# LED_Matrix.net
KiCad netlist of a schematic drawn in EAGLE
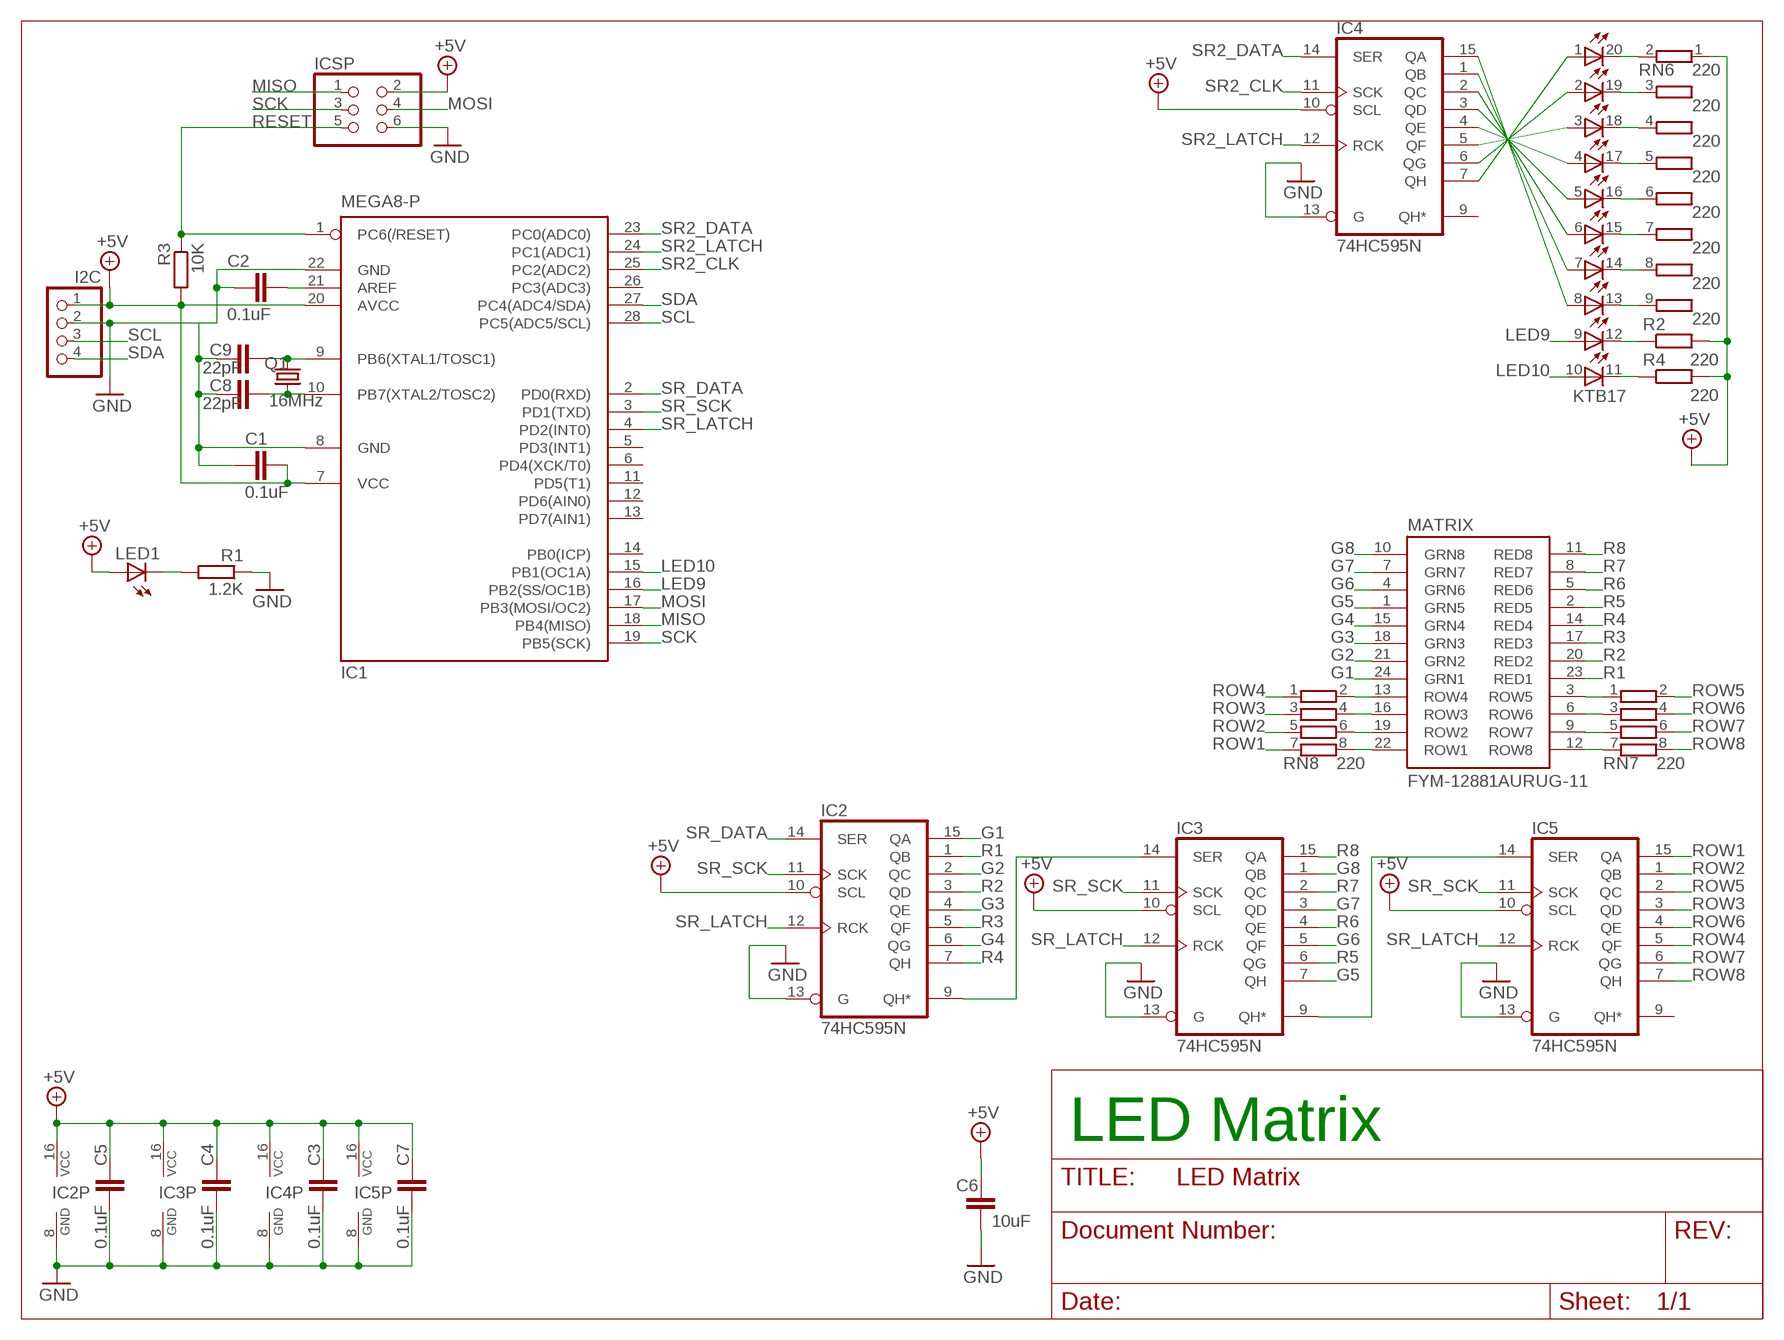
[diagram p0: schematic, sheet 1]

(export (version "E")
  (design (tool "Eeschema 10.0.6"))
  (components
    (comp (ref "-")
      (value "KTB17")
      (footprint "eagle-import:LB10")
      (libsource (lib "eagle-import") (part "LB10"))
    )
    (comp (ref "C1")
      (value "0.1uF")
      (footprint "eagle-import:C025-024X044")
      (libsource (lib "eagle-import") (part "C-EU025-024X044"))
    )
    (comp (ref "C2")
      (value "0.1uF")
      (footprint "eagle-import:C025-024X044")
      (libsource (lib "eagle-import") (part "C-EU025-024X044"))
    )
    (comp (ref "C3")
      (value "0.1uF")
      (footprint "eagle-import:C025-024X044")
      (libsource (lib "eagle-import") (part "C-EU025-024X044"))
    )
    (comp (ref "C4")
      (value "0.1uF")
      (footprint "eagle-import:C025-024X044")
      (libsource (lib "eagle-import") (part "C-EU025-024X044"))
    )
    (comp (ref "C5")
      (value "0.1uF")
      (footprint "eagle-import:C025-024X044")
      (libsource (lib "eagle-import") (part "C-EU025-024X044"))
    )
    (comp (ref "C6")
      (value "10uF")
      (footprint "eagle-import:C025-024X044")
      (libsource (lib "eagle-import") (part "C-EU025-024X044"))
    )
    (comp (ref "C7")
      (value "0.1uF")
      (footprint "eagle-import:C025-024X044")
      (libsource (lib "eagle-import") (part "C-EU025-024X044"))
    )
    (comp (ref "C8")
      (value "22pF")
      (footprint "eagle-import:C025-024X044")
      (libsource (lib "eagle-import") (part "C-EU025-024X044"))
    )
    (comp (ref "C9")
      (value "22pF")
      (footprint "eagle-import:C025-024X044")
      (libsource (lib "eagle-import") (part "C-EU025-024X044"))
    )
    (comp (ref "I2C")
      (value "PINHD-1X4")
      (footprint "eagle-import:1X04")
      (libsource (lib "eagle-import") (part "PINHD-1X4"))
    )
    (comp (ref "IC1")
      (value "MEGA8-P")
      (footprint "eagle-import:DIL28-3")
      (libsource (lib "eagle-import") (part "MEGA8-P"))
    )
    (comp (ref "IC2")
      (value "74HC595N")
      (footprint "eagle-import:DIL16")
      (libsource (lib "eagle-import") (part "74595NHC"))
    )
    (comp (ref "IC3")
      (value "74HC595N")
      (footprint "eagle-import:DIL16")
      (libsource (lib "eagle-import") (part "74595NHC"))
    )
    (comp (ref "IC4")
      (value "74HC595N")
      (footprint "eagle-import:DIL16")
      (libsource (lib "eagle-import") (part "74595NHC"))
    )
    (comp (ref "IC5")
      (value "74HC595N")
      (footprint "eagle-import:DIL16")
      (libsource (lib "eagle-import") (part "74595NHC"))
    )
    (comp (ref "ICSP")
      (value "PINHD-2X3")
      (footprint "eagle-import:2X03")
      (libsource (lib "eagle-import") (part "PINHD-2X3"))
    )
    (comp (ref "LED1")
      (value "LED5MM")
      (footprint "eagle-import:LED5MM")
      (libsource (lib "eagle-import") (part "LED5MM"))
    )
    (comp (ref "MATRIX")
      (value "FYM-12881AURUG-11")
      (footprint "eagle-import:YSM-1288CR3G2C")
      (libsource (lib "eagle-import") (part "YSM-1288CR3G2C"))
    )
    (comp (ref "Q1")
      (value "16MHz")
      (footprint "eagle-import:HC49_S")
      (libsource (lib "eagle-import") (part "CRYSTALHC49S"))
    )
    (comp (ref "R1")
      (value "1.2K")
      (footprint "eagle-import:0207_2V")
      (libsource (lib "eagle-import") (part "R-EU_0207/2V"))
    )
    (comp (ref "R2")
      (value "220")
      (footprint "eagle-import:0207_2V")
      (libsource (lib "eagle-import") (part "R-EU_0207/2V"))
    )
    (comp (ref "R3")
      (value "10K")
      (footprint "eagle-import:0207_2V")
      (libsource (lib "eagle-import") (part "R-EU_0207/2V"))
    )
    (comp (ref "R4")
      (value "220")
      (footprint "eagle-import:0207_2V")
      (libsource (lib "eagle-import") (part "R-EU_0207/2V"))
    )
    (comp (ref "RN6")
      (value "220")
      (footprint "eagle-import:SIL9")
      (libsource (lib "eagle-import") (part "GE08RP"))
    )
    (comp (ref "RN7")
      (value "220")
      (footprint "eagle-import:SIL8")
      (libsource (lib "eagle-import") (part "E4RP"))
    )
    (comp (ref "RN8")
      (value "220")
      (footprint "eagle-import:SIL8")
      (libsource (lib "eagle-import") (part "E4RP"))
    )
  )
  (nets
    (net (code "1") (name "+5V") (class "Default")
      (node (ref "C1") (pin "2") (pinfunction "2_2") (pintype "passive"))
      (node (ref "C3") (pin "1") (pinfunction "1_1") (pintype "passive"))
      (node (ref "C4") (pin "1") (pinfunction "1_1") (pintype "passive"))
      (node (ref "C5") (pin "1") (pinfunction "1_1") (pintype "passive"))
      (node (ref "C6") (pin "1") (pinfunction "1_1") (pintype "passive"))
      (node (ref "C7") (pin "1") (pinfunction "1_1") (pintype "passive"))
      (node (ref "I2C") (pin "1") (pinfunction "1_1") (pintype "passive"))
      (node (ref "IC1") (pin "20") (pinfunction "AVCC_20") (pintype "power_in"))
      (node (ref "IC1") (pin "7") (pinfunction "VCC_7") (pintype "power_in"))
      (node (ref "IC2") (pin "10") (pinfunction "SCL_10") (pintype "input"))
      (node (ref "IC2") (pin "16") (pinfunction "VCC_16") (pintype "power_in"))
      (node (ref "IC3") (pin "10") (pinfunction "SCL_10") (pintype "input"))
      (node (ref "IC3") (pin "16") (pinfunction "VCC_16") (pintype "power_in"))
      (node (ref "IC4") (pin "10") (pinfunction "SCL_10") (pintype "input"))
      (node (ref "IC4") (pin "16") (pinfunction "VCC_16") (pintype "power_in"))
      (node (ref "IC5") (pin "10") (pinfunction "SCL_10") (pintype "input"))
      (node (ref "IC5") (pin "16") (pinfunction "VCC_16") (pintype "power_in"))
      (node (ref "ICSP") (pin "2") (pinfunction "2_2") (pintype "passive"))
      (node (ref "LED1") (pin "A") (pinfunction "A_A") (pintype "passive"))
      (node (ref "R2") (pin "2") (pinfunction "2_2") (pintype "passive"))
      (node (ref "R3") (pin "2") (pinfunction "2_2") (pintype "passive"))
      (node (ref "R4") (pin "2") (pinfunction "2_2") (pintype "passive"))
      (node (ref "RN6") (pin "1") (pinfunction "1_1") (pintype "passive"))
    )
    (net (code "2") (name "/G1") (class "Default")
      (node (ref "IC2") (pin "15") (pinfunction "QA_15") (pintype "tri_state"))
      (node (ref "MATRIX") (pin "24") (pinfunction "GRN1_24") (pintype "bidirectional"))
    )
    (net (code "3") (name "/G2") (class "Default")
      (node (ref "IC2") (pin "2") (pinfunction "QC_2") (pintype "tri_state"))
      (node (ref "MATRIX") (pin "21") (pinfunction "GRN2_21") (pintype "bidirectional"))
    )
    (net (code "4") (name "/G3") (class "Default")
      (node (ref "IC2") (pin "4") (pinfunction "QE_4") (pintype "tri_state"))
      (node (ref "MATRIX") (pin "18") (pinfunction "GRN3_18") (pintype "bidirectional"))
    )
    (net (code "5") (name "/G4") (class "Default")
      (node (ref "IC2") (pin "6") (pinfunction "QG_6") (pintype "tri_state"))
      (node (ref "MATRIX") (pin "15") (pinfunction "GRN4_15") (pintype "bidirectional"))
    )
    (net (code "6") (name "/G5") (class "Default")
      (node (ref "IC3") (pin "7") (pinfunction "QH_7") (pintype "tri_state"))
      (node (ref "MATRIX") (pin "1") (pinfunction "GRN5_1") (pintype "bidirectional"))
    )
    (net (code "7") (name "/G6") (class "Default")
      (node (ref "IC3") (pin "5") (pinfunction "QF_5") (pintype "tri_state"))
      (node (ref "MATRIX") (pin "4") (pinfunction "GRN6_4") (pintype "bidirectional"))
    )
    (net (code "8") (name "/G7") (class "Default")
      (node (ref "IC3") (pin "3") (pinfunction "QD_3") (pintype "tri_state"))
      (node (ref "MATRIX") (pin "7") (pinfunction "GRN7_7") (pintype "bidirectional"))
    )
    (net (code "9") (name "/G8") (class "Default")
      (node (ref "IC3") (pin "1") (pinfunction "QB_1") (pintype "tri_state"))
      (node (ref "MATRIX") (pin "10") (pinfunction "GRN8_10") (pintype "bidirectional"))
    )
    (net (code "10") (name "/LED9") (class "Default")
      (node (ref "-") (pin "9") (pinfunction "A_9") (pintype "passive"))
      (node (ref "IC1") (pin "16") (pinfunction "PB2(SS/OC1B)_16") (pintype "bidirectional"))
    )
    (net (code "11") (name "/LED10") (class "Default")
      (node (ref "-") (pin "10") (pinfunction "A_10") (pintype "passive"))
      (node (ref "IC1") (pin "15") (pinfunction "PB1(OC1A)_15") (pintype "bidirectional"))
    )
    (net (code "12") (name "/MISO") (class "Default")
      (node (ref "IC1") (pin "18") (pinfunction "PB4(MISO)_18") (pintype "bidirectional"))
      (node (ref "ICSP") (pin "1") (pinfunction "1_1") (pintype "passive"))
    )
    (net (code "13") (name "/MOSI") (class "Default")
      (node (ref "IC1") (pin "17") (pinfunction "PB3(MOSI/OC2)_17") (pintype "bidirectional"))
      (node (ref "ICSP") (pin "4") (pinfunction "4_4") (pintype "passive"))
    )
    (net (code "14") (name "/R1") (class "Default")
      (node (ref "IC2") (pin "1") (pinfunction "QB_1") (pintype "tri_state"))
      (node (ref "MATRIX") (pin "23") (pinfunction "RED1_23") (pintype "bidirectional"))
    )
    (net (code "15") (name "/R2") (class "Default")
      (node (ref "IC2") (pin "3") (pinfunction "QD_3") (pintype "tri_state"))
      (node (ref "MATRIX") (pin "20") (pinfunction "RED2_20") (pintype "bidirectional"))
    )
    (net (code "16") (name "/R3") (class "Default")
      (node (ref "IC2") (pin "5") (pinfunction "QF_5") (pintype "tri_state"))
      (node (ref "MATRIX") (pin "17") (pinfunction "RED3_17") (pintype "bidirectional"))
    )
    (net (code "17") (name "/R4") (class "Default")
      (node (ref "IC2") (pin "7") (pinfunction "QH_7") (pintype "tri_state"))
      (node (ref "MATRIX") (pin "14") (pinfunction "RED4_14") (pintype "bidirectional"))
    )
    (net (code "18") (name "/R5") (class "Default")
      (node (ref "IC3") (pin "6") (pinfunction "QG_6") (pintype "tri_state"))
      (node (ref "MATRIX") (pin "2") (pinfunction "RED5_2") (pintype "bidirectional"))
    )
    (net (code "19") (name "/R6") (class "Default")
      (node (ref "IC3") (pin "4") (pinfunction "QE_4") (pintype "tri_state"))
      (node (ref "MATRIX") (pin "5") (pinfunction "RED6_5") (pintype "bidirectional"))
    )
    (net (code "20") (name "/R7") (class "Default")
      (node (ref "IC3") (pin "2") (pinfunction "QC_2") (pintype "tri_state"))
      (node (ref "MATRIX") (pin "8") (pinfunction "RED7_8") (pintype "bidirectional"))
    )
    (net (code "21") (name "/R8") (class "Default")
      (node (ref "IC3") (pin "15") (pinfunction "QA_15") (pintype "tri_state"))
      (node (ref "MATRIX") (pin "11") (pinfunction "RED8_11") (pintype "bidirectional"))
    )
    (net (code "22") (name "/RESET") (class "Default")
      (node (ref "IC1") (pin "1") (pinfunction "PC6(/RESET)_1") (pintype "bidirectional"))
      (node (ref "ICSP") (pin "5") (pinfunction "5_5") (pintype "passive"))
      (node (ref "R3") (pin "1") (pinfunction "1_1") (pintype "passive"))
    )
    (net (code "23") (name "/ROW1") (class "Default")
      (node (ref "IC5") (pin "15") (pinfunction "QA_15") (pintype "tri_state"))
      (node (ref "RN8") (pin "7") (pinfunction "1_7") (pintype "passive"))
    )
    (net (code "24") (name "/ROW2") (class "Default")
      (node (ref "IC5") (pin "1") (pinfunction "QB_1") (pintype "tri_state"))
      (node (ref "RN8") (pin "5") (pinfunction "1_5") (pintype "passive"))
    )
    (net (code "25") (name "/ROW3") (class "Default")
      (node (ref "IC5") (pin "3") (pinfunction "QD_3") (pintype "tri_state"))
      (node (ref "RN8") (pin "3") (pinfunction "1_3") (pintype "passive"))
    )
    (net (code "26") (name "/ROW4") (class "Default")
      (node (ref "IC5") (pin "5") (pinfunction "QF_5") (pintype "tri_state"))
      (node (ref "RN8") (pin "1") (pinfunction "1_1") (pintype "passive"))
    )
    (net (code "27") (name "/ROW5") (class "Default")
      (node (ref "IC5") (pin "2") (pinfunction "QC_2") (pintype "tri_state"))
      (node (ref "RN7") (pin "2") (pinfunction "2_2") (pintype "passive"))
    )
    (net (code "28") (name "/ROW6") (class "Default")
      (node (ref "IC5") (pin "4") (pinfunction "QE_4") (pintype "tri_state"))
      (node (ref "RN7") (pin "4") (pinfunction "2_4") (pintype "passive"))
    )
    (net (code "29") (name "/ROW7") (class "Default")
      (node (ref "IC5") (pin "6") (pinfunction "QG_6") (pintype "tri_state"))
      (node (ref "RN7") (pin "6") (pinfunction "2_6") (pintype "passive"))
    )
    (net (code "30") (name "/ROW8") (class "Default")
      (node (ref "IC5") (pin "7") (pinfunction "QH_7") (pintype "tri_state"))
      (node (ref "RN7") (pin "8") (pinfunction "2_8") (pintype "passive"))
    )
    (net (code "31") (name "/SCK") (class "Default")
      (node (ref "IC1") (pin "19") (pinfunction "PB5(SCK)_19") (pintype "bidirectional"))
      (node (ref "ICSP") (pin "3") (pinfunction "3_3") (pintype "passive"))
    )
    (net (code "32") (name "/SCL") (class "Default")
      (node (ref "I2C") (pin "3") (pinfunction "3_3") (pintype "passive"))
      (node (ref "IC1") (pin "28") (pinfunction "PC5(ADC5/SCL)_28") (pintype "bidirectional"))
    )
    (net (code "33") (name "/SDA") (class "Default")
      (node (ref "I2C") (pin "4") (pinfunction "4_4") (pintype "passive"))
      (node (ref "IC1") (pin "27") (pinfunction "PC4(ADC4/SDA)_27") (pintype "bidirectional"))
    )
    (net (code "34") (name "/SR2_CLK") (class "Default")
      (node (ref "IC1") (pin "25") (pinfunction "PC2(ADC2)_25") (pintype "bidirectional"))
      (node (ref "IC4") (pin "11") (pinfunction "SCK_11") (pintype "input"))
    )
    (net (code "35") (name "/SR2_DATA") (class "Default")
      (node (ref "IC1") (pin "23") (pinfunction "PC0(ADC0)_23") (pintype "bidirectional"))
      (node (ref "IC4") (pin "14") (pinfunction "SER_14") (pintype "input"))
    )
    (net (code "36") (name "/SR2_LATCH") (class "Default")
      (node (ref "IC1") (pin "24") (pinfunction "PC1(ADC1)_24") (pintype "bidirectional"))
      (node (ref "IC4") (pin "12") (pinfunction "RCK_12") (pintype "input"))
    )
    (net (code "37") (name "/SR_DATA") (class "Default")
      (node (ref "IC1") (pin "2") (pinfunction "PD0(RXD)_2") (pintype "bidirectional"))
      (node (ref "IC2") (pin "14") (pinfunction "SER_14") (pintype "input"))
    )
    (net (code "38") (name "/SR_LATCH") (class "Default")
      (node (ref "IC1") (pin "4") (pinfunction "PD2(INT0)_4") (pintype "bidirectional"))
      (node (ref "IC2") (pin "12") (pinfunction "RCK_12") (pintype "input"))
      (node (ref "IC3") (pin "12") (pinfunction "RCK_12") (pintype "input"))
      (node (ref "IC5") (pin "12") (pinfunction "RCK_12") (pintype "input"))
    )
    (net (code "39") (name "/SR_SCK") (class "Default")
      (node (ref "IC1") (pin "3") (pinfunction "PD1(TXD)_3") (pintype "bidirectional"))
      (node (ref "IC2") (pin "11") (pinfunction "SCK_11") (pintype "input"))
      (node (ref "IC3") (pin "11") (pinfunction "SCK_11") (pintype "input"))
      (node (ref "IC5") (pin "11") (pinfunction "SCK_11") (pintype "input"))
    )
    (net (code "40") (name "GND") (class "Default")
      (node (ref "C1") (pin "1") (pinfunction "1_1") (pintype "passive"))
      (node (ref "C2") (pin "1") (pinfunction "1_1") (pintype "passive"))
      (node (ref "C3") (pin "2") (pinfunction "2_2") (pintype "passive"))
      (node (ref "C4") (pin "2") (pinfunction "2_2") (pintype "passive"))
      (node (ref "C5") (pin "2") (pinfunction "2_2") (pintype "passive"))
      (node (ref "C6") (pin "2") (pinfunction "2_2") (pintype "passive"))
      (node (ref "C7") (pin "2") (pinfunction "2_2") (pintype "passive"))
      (node (ref "C8") (pin "1") (pinfunction "1_1") (pintype "passive"))
      (node (ref "C9") (pin "1") (pinfunction "1_1") (pintype "passive"))
      (node (ref "I2C") (pin "2") (pinfunction "2_2") (pintype "passive"))
      (node (ref "IC1") (pin "22") (pinfunction "GND_22") (pintype "power_in"))
      (node (ref "IC1") (pin "8") (pinfunction "GND_8") (pintype "power_in"))
      (node (ref "IC2") (pin "13") (pinfunction "G_13") (pintype "input"))
      (node (ref "IC2") (pin "8") (pinfunction "GND_8") (pintype "power_in"))
      (node (ref "IC3") (pin "13") (pinfunction "G_13") (pintype "input"))
      (node (ref "IC3") (pin "8") (pinfunction "GND_8") (pintype "power_in"))
      (node (ref "IC4") (pin "13") (pinfunction "G_13") (pintype "input"))
      (node (ref "IC4") (pin "8") (pinfunction "GND_8") (pintype "power_in"))
      (node (ref "IC5") (pin "13") (pinfunction "G_13") (pintype "input"))
      (node (ref "IC5") (pin "8") (pinfunction "GND_8") (pintype "power_in"))
      (node (ref "ICSP") (pin "6") (pinfunction "6_6") (pintype "passive"))
      (node (ref "R1") (pin "1") (pinfunction "1_1") (pintype "passive"))
    )
    (net (code "41") (name "Net-(-A-A)") (class "Default")
      (node (ref "-") (pin "1") (pinfunction "A_1") (pintype "passive"))
      (node (ref "IC4") (pin "7") (pinfunction "QH_7") (pintype "tri_state"))
    )
    (net (code "42") (name "Net-(-A-C)") (class "Default")
      (node (ref "-") (pin "20") (pinfunction "C_20") (pintype "passive"))
      (node (ref "RN6") (pin "2") (pinfunction "2_2") (pintype "passive"))
    )
    (net (code "43") (name "Net-(-B-C)") (class "Default")
      (node (ref "-") (pin "11") (pinfunction "C_11") (pintype "passive"))
      (node (ref "R4") (pin "1") (pinfunction "1_1") (pintype "passive"))
    )
    (net (code "44") (name "Net-(-C-A)") (class "Default")
      (node (ref "-") (pin "2") (pinfunction "A_2") (pintype "passive"))
      (node (ref "IC4") (pin "6") (pinfunction "QG_6") (pintype "tri_state"))
    )
    (net (code "45") (name "Net-(-C-C)") (class "Default")
      (node (ref "-") (pin "19") (pinfunction "C_19") (pintype "passive"))
      (node (ref "RN6") (pin "3") (pinfunction "2_3") (pintype "passive"))
    )
    (net (code "46") (name "Net-(-D-A)") (class "Default")
      (node (ref "-") (pin "3") (pinfunction "A_3") (pintype "passive"))
      (node (ref "IC4") (pin "5") (pinfunction "QF_5") (pintype "tri_state"))
    )
    (net (code "47") (name "Net-(-D-C)") (class "Default")
      (node (ref "-") (pin "18") (pinfunction "C_18") (pintype "passive"))
      (node (ref "RN6") (pin "4") (pinfunction "2_4") (pintype "passive"))
    )
    (net (code "48") (name "Net-(-E-A)") (class "Default")
      (node (ref "-") (pin "4") (pinfunction "A_4") (pintype "passive"))
      (node (ref "IC4") (pin "4") (pinfunction "QE_4") (pintype "tri_state"))
    )
    (net (code "49") (name "Net-(-E-C)") (class "Default")
      (node (ref "-") (pin "17") (pinfunction "C_17") (pintype "passive"))
      (node (ref "RN6") (pin "5") (pinfunction "2_5") (pintype "passive"))
    )
    (net (code "50") (name "Net-(-F-A)") (class "Default")
      (node (ref "-") (pin "5") (pinfunction "A_5") (pintype "passive"))
      (node (ref "IC4") (pin "3") (pinfunction "QD_3") (pintype "tri_state"))
    )
    (net (code "51") (name "Net-(-F-C)") (class "Default")
      (node (ref "-") (pin "16") (pinfunction "C_16") (pintype "passive"))
      (node (ref "RN6") (pin "6") (pinfunction "2_6") (pintype "passive"))
    )
    (net (code "52") (name "Net-(-G-A)") (class "Default")
      (node (ref "-") (pin "6") (pinfunction "A_6") (pintype "passive"))
      (node (ref "IC4") (pin "2") (pinfunction "QC_2") (pintype "tri_state"))
    )
    (net (code "53") (name "Net-(-G-C)") (class "Default")
      (node (ref "-") (pin "15") (pinfunction "C_15") (pintype "passive"))
      (node (ref "RN6") (pin "7") (pinfunction "2_7") (pintype "passive"))
    )
    (net (code "54") (name "Net-(-H-A)") (class "Default")
      (node (ref "-") (pin "7") (pinfunction "A_7") (pintype "passive"))
      (node (ref "IC4") (pin "1") (pinfunction "QB_1") (pintype "tri_state"))
    )
    (net (code "55") (name "Net-(-H-C)") (class "Default")
      (node (ref "-") (pin "14") (pinfunction "C_14") (pintype "passive"))
      (node (ref "RN6") (pin "8") (pinfunction "2_8") (pintype "passive"))
    )
    (net (code "56") (name "Net-(-I-A)") (class "Default")
      (node (ref "-") (pin "8") (pinfunction "A_8") (pintype "passive"))
      (node (ref "IC4") (pin "15") (pinfunction "QA_15") (pintype "tri_state"))
    )
    (net (code "57") (name "Net-(-I-C)") (class "Default")
      (node (ref "-") (pin "13") (pinfunction "C_13") (pintype "passive"))
      (node (ref "RN6") (pin "9") (pinfunction "2_9") (pintype "passive"))
    )
    (net (code "58") (name "Net-(-J-C)") (class "Default")
      (node (ref "-") (pin "12") (pinfunction "C_12") (pintype "passive"))
      (node (ref "R2") (pin "1") (pinfunction "1_1") (pintype "passive"))
    )
    (net (code "59") (name "Net-(IC1-AREF)") (class "Default")
      (node (ref "C2") (pin "2") (pinfunction "2_2") (pintype "passive"))
      (node (ref "IC1") (pin "21") (pinfunction "AREF_21") (pintype "passive"))
    )
    (net (code "60") (name "Net-(IC1-PB6(XTAL1{slash}TOSC1))") (class "Default")
      (node (ref "C9") (pin "2") (pinfunction "2_2") (pintype "passive"))
      (node (ref "IC1") (pin "9") (pinfunction "PB6(XTAL1/TOSC1)_9") (pintype "bidirectional"))
      (node (ref "Q1") (pin "2") (pinfunction "2_2") (pintype "passive"))
    )
    (net (code "61") (name "Net-(IC1-PB7(XTAL2{slash}TOSC2))") (class "Default")
      (node (ref "C8") (pin "2") (pinfunction "2_2") (pintype "passive"))
      (node (ref "IC1") (pin "10") (pinfunction "PB7(XTAL2/TOSC2)_10") (pintype "bidirectional"))
      (node (ref "Q1") (pin "1") (pinfunction "1_1") (pintype "passive"))
    )
    (net (code "62") (name "Net-(IC2A-QH*)") (class "Default")
      (node (ref "IC2") (pin "9") (pinfunction "QH*_9") (pintype "tri_state"))
      (node (ref "IC3") (pin "14") (pinfunction "SER_14") (pintype "input"))
    )
    (net (code "63") (name "Net-(IC3A-QH*)") (class "Default")
      (node (ref "IC3") (pin "9") (pinfunction "QH*_9") (pintype "tri_state"))
      (node (ref "IC5") (pin "14") (pinfunction "SER_14") (pintype "input"))
    )
    (net (code "64") (name "Net-(LED1-C)") (class "Default")
      (node (ref "LED1") (pin "K") (pinfunction "C_K") (pintype "passive"))
      (node (ref "R1") (pin "2") (pinfunction "2_2") (pintype "passive"))
    )
    (net (code "65") (name "Net-(MATRIX-ROW1)") (class "Default")
      (node (ref "MATRIX") (pin "22") (pinfunction "ROW1_22") (pintype "bidirectional"))
      (node (ref "RN8") (pin "8") (pinfunction "2_8") (pintype "passive"))
    )
    (net (code "66") (name "Net-(MATRIX-ROW2)") (class "Default")
      (node (ref "MATRIX") (pin "19") (pinfunction "ROW2_19") (pintype "bidirectional"))
      (node (ref "RN8") (pin "6") (pinfunction "2_6") (pintype "passive"))
    )
    (net (code "67") (name "Net-(MATRIX-ROW3)") (class "Default")
      (node (ref "MATRIX") (pin "16") (pinfunction "ROW3_16") (pintype "bidirectional"))
      (node (ref "RN8") (pin "4") (pinfunction "2_4") (pintype "passive"))
    )
    (net (code "68") (name "Net-(MATRIX-ROW4)") (class "Default")
      (node (ref "MATRIX") (pin "13") (pinfunction "ROW4_13") (pintype "bidirectional"))
      (node (ref "RN8") (pin "2") (pinfunction "2_2") (pintype "passive"))
    )
    (net (code "69") (name "Net-(MATRIX-ROW5)") (class "Default")
      (node (ref "MATRIX") (pin "3") (pinfunction "ROW5_3") (pintype "bidirectional"))
      (node (ref "RN7") (pin "1") (pinfunction "1_1") (pintype "passive"))
    )
    (net (code "70") (name "Net-(MATRIX-ROW6)") (class "Default")
      (node (ref "MATRIX") (pin "6") (pinfunction "ROW6_6") (pintype "bidirectional"))
      (node (ref "RN7") (pin "3") (pinfunction "1_3") (pintype "passive"))
    )
    (net (code "71") (name "Net-(MATRIX-ROW7)") (class "Default")
      (node (ref "MATRIX") (pin "9") (pinfunction "ROW7_9") (pintype "bidirectional"))
      (node (ref "RN7") (pin "5") (pinfunction "1_5") (pintype "passive"))
    )
    (net (code "72") (name "Net-(MATRIX-ROW8)") (class "Default")
      (node (ref "MATRIX") (pin "12") (pinfunction "ROW8_12") (pintype "bidirectional"))
      (node (ref "RN7") (pin "7") (pinfunction "1_7") (pintype "passive"))
    )
    (net (code "73") (name "unconnected-(IC1-PB0(ICP)-Pad14)") (class "Default")
      (node (ref "IC1") (pin "14") (pinfunction "PB0(ICP)_14") (pintype "bidirectional"))
    )
    (net (code "74") (name "unconnected-(IC1-PC3(ADC3)-Pad26)") (class "Default")
      (node (ref "IC1") (pin "26") (pinfunction "PC3(ADC3)_26") (pintype "bidirectional"))
    )
    (net (code "75") (name "unconnected-(IC1-PD3(INT1)-Pad5)") (class "Default")
      (node (ref "IC1") (pin "5") (pinfunction "PD3(INT1)_5") (pintype "bidirectional"))
    )
    (net (code "76") (name "unconnected-(IC1-PD4(XCK{slash}T0)-Pad6)") (class "Default")
      (node (ref "IC1") (pin "6") (pinfunction "PD4(XCK/T0)_6") (pintype "bidirectional"))
    )
    (net (code "77") (name "unconnected-(IC1-PD5(T1)-Pad11)") (class "Default")
      (node (ref "IC1") (pin "11") (pinfunction "PD5(T1)_11") (pintype "bidirectional"))
    )
    (net (code "78") (name "unconnected-(IC1-PD6(AIN0)-Pad12)") (class "Default")
      (node (ref "IC1") (pin "12") (pinfunction "PD6(AIN0)_12") (pintype "bidirectional"))
    )
    (net (code "79") (name "unconnected-(IC1-PD7(AIN1)-Pad13)") (class "Default")
      (node (ref "IC1") (pin "13") (pinfunction "PD7(AIN1)_13") (pintype "bidirectional"))
    )
    (net (code "80") (name "unconnected-(IC4A-QH*-Pad9)") (class "Default")
      (node (ref "IC4") (pin "9") (pinfunction "QH*_9") (pintype "tri_state"))
    )
    (net (code "81") (name "unconnected-(IC5A-QH*-Pad9)") (class "Default")
      (node (ref "IC5") (pin "9") (pinfunction "QH*_9") (pintype "tri_state"))
    )
  )
)
